# lab2_kapustin_buck.net
KiCad netlist of a schematic drawn in Altium Designer
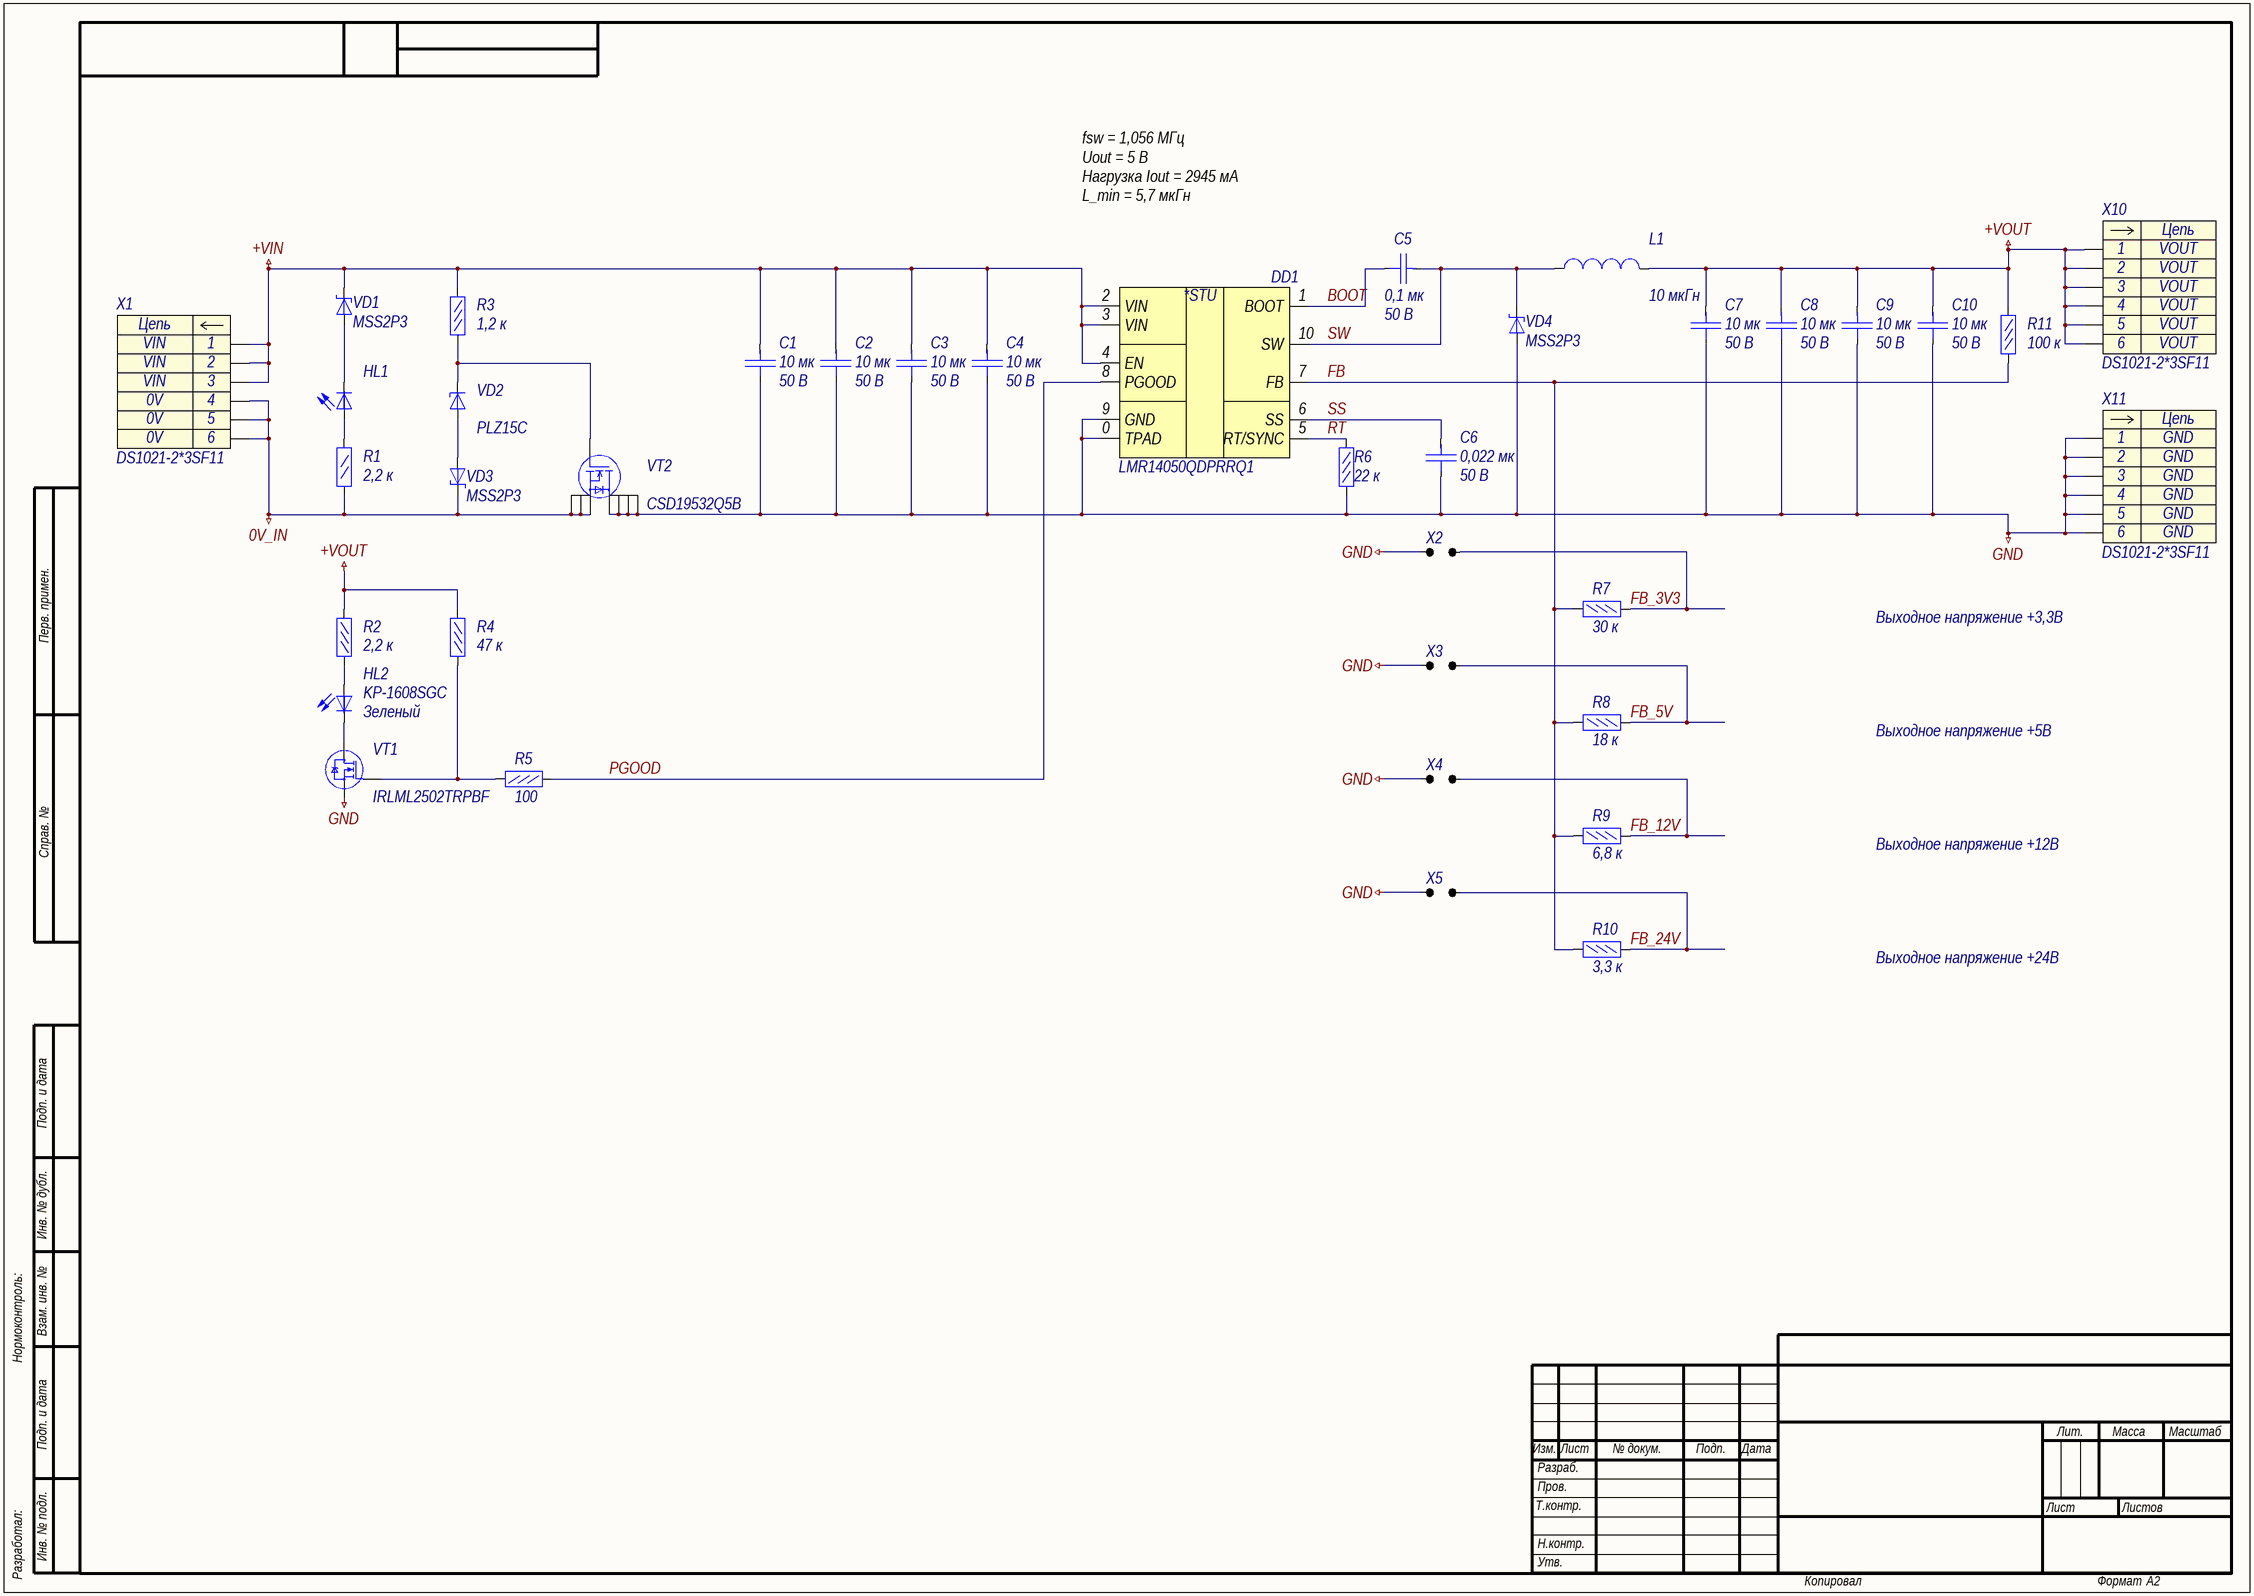
[diagram p0: lab2_kapustin_buck.SchDoc]

(export (version "E")
  (design (tool "Eeschema 10.0.6"))
  (components
    (comp (ref "C1")
      (value "10 мк")
      (footprint "C1206")
      (description "Конденсатор")
      (fields (field (name "НАПРЯЖЕНИЕ") "50 В"))
      (libsource (lib "kravt_lib") (part "c"))
    )
    (comp (ref "C2")
      (value "10 мк")
      (footprint "C1206")
      (description "Конденсатор")
      (fields (field (name "НАПРЯЖЕНИЕ") "50 В"))
      (libsource (lib "kravt_lib") (part "c"))
    )
    (comp (ref "C3")
      (value "10 мк")
      (footprint "C1206")
      (description "Конденсатор")
      (fields (field (name "НАПРЯЖЕНИЕ") "50 В"))
      (libsource (lib "kravt_lib") (part "c"))
    )
    (comp (ref "C4")
      (value "10 мк")
      (footprint "C1206")
      (description "Конденсатор")
      (fields (field (name "НАПРЯЖЕНИЕ") "50 В"))
      (libsource (lib "kravt_lib") (part "c"))
    )
    (comp (ref "C5")
      (value "0,1 мк")
      (footprint "C0603")
      (description "Конденсатор")
      (fields (field (name "НАПРЯЖЕНИЕ") "50 В"))
      (libsource (lib "kravt_lib") (part "c"))
    )
    (comp (ref "C6")
      (value "0,022 мк")
      (footprint "C0603")
      (description "Конденсатор")
      (fields (field (name "НАПРЯЖЕНИЕ") "50 В"))
      (libsource (lib "kravt_lib") (part "c"))
    )
    (comp (ref "C7")
      (value "10 мк")
      (footprint "C1206")
      (description "Конденсатор")
      (fields (field (name "НАПРЯЖЕНИЕ") "50 В"))
      (libsource (lib "kravt_lib") (part "c"))
    )
    (comp (ref "C8")
      (value "10 мк")
      (footprint "C1206")
      (description "Конденсатор")
      (fields (field (name "НАПРЯЖЕНИЕ") "50 В"))
      (libsource (lib "kravt_lib") (part "c"))
    )
    (comp (ref "C9")
      (value "10 мк")
      (footprint "C1206")
      (description "Конденсатор")
      (fields (field (name "НАПРЯЖЕНИЕ") "50 В"))
      (libsource (lib "kravt_lib") (part "c"))
    )
    (comp (ref "C10")
      (value "10 мк")
      (footprint "C1206")
      (description "Конденсатор")
      (fields (field (name "НАПРЯЖЕНИЕ") "50 В"))
      (libsource (lib "kravt_lib") (part "c"))
    )
    (comp (ref "DD1")
      (value "LMR14050QDPRRQ1")
      (footprint "WSON-10")
      (libsource (lib "kravt_lib") (part "LMR14050QDPRRQ1"))
    )
    (comp (ref "HL1")
      (value "KP-1608EC")
      (footprint "D0603")
      (libsource (lib "kravt_lib") (part "DIODE_LED"))
    )
    (comp (ref "HL2")
      (value "KP-1608SGC")
      (footprint "D0603")
      (fields (field (name "НАИМЕНОВАНИЕ") "KP-1608SGC") (field (name "ЦВЕТ") "Зеленый"))
      (libsource (lib "kravt_lib") (part "DIODE_LED"))
    )
    (comp (ref "L1") (value "10 мкГн") (footprint "IHLP2525CZ") (libsource (lib "kravt_lib") (part "L_CORE")))
    (comp (ref "R1")
      (value "2,2 к")
      (footprint "R0805")
      (description "Резистор 0,125Вт")
      (libsource (lib "kravt_lib") (part "R-0.125W"))
    )
    (comp (ref "R2")
      (value "2,2 к")
      (footprint "R0603")
      (description "Резистор 0,063Вт")
      (fields (field (name "НОМИНАЛ") "2,2 к"))
      (libsource (lib "kravt_lib") (part "R-0.063W"))
    )
    (comp (ref "R3")
      (value "1,2 к")
      (footprint "R0603")
      (description "Резистор 0,063Вт")
      (libsource (lib "") (part "R-0.063W_2"))
    )
    (comp (ref "R4")
      (value "47 к")
      (footprint "R0603")
      (description "Резистор 0,063Вт")
      (fields (field (name "НОМИНАЛ") "47 к"))
      (libsource (lib "kravt_lib") (part "R-0.063W"))
    )
    (comp (ref "R5")
      (value "100")
      (footprint "R0603")
      (description "Резистор 0,063Вт")
      (fields (field (name "НОМИНАЛ") "100"))
      (libsource (lib "") (part "R-0.063W_1"))
    )
    (comp (ref "R6")
      (value "22 к")
      (footprint "R0603")
      (description "Резистор 0,063Вт")
      (libsource (lib "") (part "R-0.063W_1"))
    )
    (comp (ref "R7")
      (value "30 к")
      (footprint "R0603")
      (description "Резистор 0,063Вт")
      (libsource (lib "kravt_lib") (part "R-0.063W"))
    )
    (comp (ref "R8")
      (value "18 к")
      (footprint "R0603")
      (description "Резистор 0,063Вт")
      (fields (field (name "НОМИНАЛ") "18 к"))
      (libsource (lib "") (part "R-0.063W_3"))
    )
    (comp (ref "R9")
      (value "6,8 к")
      (footprint "R0603")
      (description "Резистор 0,063Вт")
      (libsource (lib "kravt_lib") (part "R-0.063W"))
    )
    (comp (ref "R10")
      (value "3,3 к")
      (footprint "R0603")
      (description "Резистор 0,063Вт")
      (libsource (lib "kravt_lib") (part "R-0.063W"))
    )
    (comp (ref "R11")
      (value "100 к")
      (footprint "R0603")
      (description "Резистор 0,063Вт")
      (fields (field (name "НОМИНАЛ") "100 к"))
      (libsource (lib "") (part "R-0.063W_2"))
    )
    (comp (ref "VD1")
      (value "MSS2P3")
      (footprint "DO-219AD")
      (libsource (lib "kravt_lib") (part "DIODE_SHOTTKY"))
    )
    (comp (ref "VD2")
      (value "PLZ15C")
      (footprint "DO-219AC")
      (libsource (lib "kravt_lib") (part "DIODE_ZENER"))
    )
    (comp (ref "VD3")
      (value "MSS2P3")
      (footprint "DO-219AD")
      (libsource (lib "kravt_lib") (part "DIODE_SHOTTKY"))
    )
    (comp (ref "VD4")
      (value "MSS2P3")
      (footprint "DO-219AD")
      (libsource (lib "kravt_lib") (part "DIODE_SHOTTKY"))
    )
    (comp (ref "VT1")
      (value "IRLML2502TRPBF")
      (footprint "SOT23-3")
      (libsource (lib "kravt_lib") (part "MOSFET-N-1G-2S-3D"))
    )
    (comp (ref "VT2")
      (value "CSD19532Q5B")
      (footprint "SON-8P")
      (libsource (lib "kravt_lib") (part "MOSFET-N-123S-4G-5678D"))
    )
    (comp (ref "X1")
      (value "DS1021-2*3SF11")
      (footprint "PLS-2,54-2X3-THT-V")
      (libsource (lib "") (part "HEADER-6_PLG_1"))
    )
    (comp (ref "X2")
      (value "Перемычка запаиваемая 3x1")
      (footprint "JUMPER_SOLDERED_3X1")
      (libsource (lib "kravt_lib") (part "JUMPER_SOLDERED"))
    )
    (comp (ref "X3")
      (value "Перемычка запаиваемая 3x1")
      (footprint "JUMPER_SOLDERED_3X1")
      (libsource (lib "kravt_lib") (part "JUMPER_SOLDERED"))
    )
    (comp (ref "X4")
      (value "Перемычка запаиваемая 3x1")
      (footprint "JUMPER_SOLDERED_3X1")
      (libsource (lib "kravt_lib") (part "JUMPER_SOLDERED"))
    )
    (comp (ref "X5")
      (value "Перемычка запаиваемая 3x1")
      (footprint "JUMPER_SOLDERED_3X1")
      (libsource (lib "kravt_lib") (part "JUMPER_SOLDERED"))
    )
    (comp (ref "X10")
      (value "DS1021-2*3SF11")
      (footprint "PLS-2,54-2X3-THT-V")
      (libsource (lib "kravt_lib") (part "HEADER-6_PLG"))
    )
    (comp (ref "X11")
      (value "DS1021-2*3SF11")
      (footprint "PLS-2,54-2X3-THT-V")
      (libsource (lib "kravt_lib") (part "HEADER-6_PLG"))
    )
  )
  (nets
    (net (code "1") (name "+VIN") (class "Default")
      (node (ref "C1") (pin "2") (pinfunction "2_2") (pintype "passive"))
      (node (ref "C2") (pin "2") (pinfunction "2_2") (pintype "passive"))
      (node (ref "C3") (pin "2") (pinfunction "2_2") (pintype "passive"))
      (node (ref "C4") (pin "2") (pinfunction "2_2") (pintype "passive"))
      (node (ref "DD1") (pin "2") (pinfunction "VIN_2") (pintype "passive"))
      (node (ref "DD1") (pin "3") (pinfunction "VIN_3") (pintype "passive"))
      (node (ref "DD1") (pin "4") (pinfunction "EN_4") (pintype "passive"))
      (node (ref "R3") (pin "2") (pinfunction "2_2") (pintype "passive"))
      (node (ref "VD1") (pin "2") (pinfunction "K_2") (pintype "passive"))
      (node (ref "X1") (pin "1") (pinfunction "1_1") (pintype "passive"))
      (node (ref "X1") (pin "2") (pinfunction "2_2") (pintype "passive"))
      (node (ref "X1") (pin "3") (pinfunction "3_3") (pintype "passive"))
    )
    (net (code "2") (name "+VOUT") (class "Default")
      (node (ref "C10") (pin "2") (pinfunction "2_2") (pintype "passive"))
      (node (ref "C7") (pin "2") (pinfunction "2_2") (pintype "passive"))
      (node (ref "C8") (pin "2") (pinfunction "2_2") (pintype "passive"))
      (node (ref "C9") (pin "2") (pinfunction "2_2") (pintype "passive"))
      (node (ref "L1") (pin "2") (pinfunction "2_2") (pintype "passive"))
      (node (ref "R11") (pin "2") (pinfunction "2_2") (pintype "passive"))
      (node (ref "R2") (pin "2") (pinfunction "2_2") (pintype "passive"))
      (node (ref "R4") (pin "2") (pinfunction "2_2") (pintype "passive"))
      (node (ref "X10") (pin "1") (pinfunction "1_1") (pintype "passive"))
      (node (ref "X10") (pin "2") (pinfunction "2_2") (pintype "passive"))
      (node (ref "X10") (pin "3") (pinfunction "3_3") (pintype "passive"))
      (node (ref "X10") (pin "4") (pinfunction "4_4") (pintype "passive"))
      (node (ref "X10") (pin "5") (pinfunction "5_5") (pintype "passive"))
      (node (ref "X10") (pin "6") (pinfunction "6_6") (pintype "passive"))
    )
    (net (code "3") (name "/BOOT") (class "Default")
      (node (ref "C5") (pin "1") (pinfunction "1_1") (pintype "passive"))
      (node (ref "DD1") (pin "1") (pinfunction "BOOT_1") (pintype "passive"))
    )
    (net (code "4") (name "/FB") (class "Default")
      (node (ref "DD1") (pin "7") (pinfunction "FB_7") (pintype "passive"))
      (node (ref "R10") (pin "1") (pinfunction "1_1") (pintype "passive"))
      (node (ref "R11") (pin "1") (pinfunction "1_1") (pintype "passive"))
      (node (ref "R7") (pin "1") (pinfunction "1_1") (pintype "passive"))
      (node (ref "R8") (pin "2") (pinfunction "2_2") (pintype "passive"))
      (node (ref "R9") (pin "1") (pinfunction "1_1") (pintype "passive"))
    )
    (net (code "5") (name "/FB_3V3") (class "Default")
      (node (ref "R7") (pin "2") (pinfunction "2_2") (pintype "passive"))
      (node (ref "X2") (pin "2") (pinfunction "2_2") (pintype "passive"))
    )
    (net (code "6") (name "/FB_5V") (class "Default")
      (node (ref "R8") (pin "1") (pinfunction "1_1") (pintype "passive"))
      (node (ref "X3") (pin "2") (pinfunction "2_2") (pintype "passive"))
    )
    (net (code "7") (name "/FB_12V") (class "Default")
      (node (ref "R9") (pin "2") (pinfunction "2_2") (pintype "passive"))
      (node (ref "X4") (pin "2") (pinfunction "2_2") (pintype "passive"))
    )
    (net (code "8") (name "/FB_24V") (class "Default")
      (node (ref "R10") (pin "2") (pinfunction "2_2") (pintype "passive"))
      (node (ref "X5") (pin "2") (pinfunction "2_2") (pintype "passive"))
    )
    (net (code "9") (name "/PGOOD") (class "Default")
      (node (ref "DD1") (pin "8") (pinfunction "PGOOD_8") (pintype "passive"))
      (node (ref "R5") (pin "1") (pinfunction "1_1") (pintype "passive"))
    )
    (net (code "10") (name "/RT") (class "Default")
      (node (ref "DD1") (pin "5") (pinfunction "RT/SYNC_5") (pintype "passive"))
      (node (ref "R6") (pin "1") (pinfunction "1_1") (pintype "passive"))
    )
    (net (code "11") (name "/SS") (class "Default")
      (node (ref "C6") (pin "2") (pinfunction "2_2") (pintype "passive"))
      (node (ref "DD1") (pin "6") (pinfunction "SS_6") (pintype "passive"))
    )
    (net (code "12") (name "/SW") (class "Default")
      (node (ref "C5") (pin "2") (pinfunction "2_2") (pintype "passive"))
      (node (ref "DD1") (pin "10") (pinfunction "SW_10") (pintype "passive"))
      (node (ref "L1") (pin "1") (pinfunction "1_1") (pintype "passive"))
      (node (ref "VD4") (pin "2") (pinfunction "K_2") (pintype "passive"))
    )
    (net (code "13") (name "0V_IN") (class "Default")
      (node (ref "R1") (pin "1") (pinfunction "1_1") (pintype "passive"))
      (node (ref "VD3") (pin "2") (pinfunction "K_2") (pintype "passive"))
      (node (ref "VT2") (pin "S") (pinfunction "S_S") (pintype "passive"))
      (node (ref "X1") (pin "4") (pinfunction "4_4") (pintype "passive"))
      (node (ref "X1") (pin "5") (pinfunction "5_5") (pintype "passive"))
      (node (ref "X1") (pin "6") (pinfunction "6_6") (pintype "passive"))
    )
    (net (code "14") (name "GND") (class "Default")
      (node (ref "C1") (pin "1") (pinfunction "1_1") (pintype "passive"))
      (node (ref "C10") (pin "1") (pinfunction "1_1") (pintype "passive"))
      (node (ref "C2") (pin "1") (pinfunction "1_1") (pintype "passive"))
      (node (ref "C3") (pin "1") (pinfunction "1_1") (pintype "passive"))
      (node (ref "C4") (pin "1") (pinfunction "1_1") (pintype "passive"))
      (node (ref "C6") (pin "1") (pinfunction "1_1") (pintype "passive"))
      (node (ref "C7") (pin "1") (pinfunction "1_1") (pintype "passive"))
      (node (ref "C8") (pin "1") (pinfunction "1_1") (pintype "passive"))
      (node (ref "C9") (pin "1") (pinfunction "1_1") (pintype "passive"))
      (node (ref "DD1") (pin "0") (pinfunction "TPAD_0") (pintype "passive"))
      (node (ref "DD1") (pin "9") (pinfunction "GND_9") (pintype "passive"))
      (node (ref "R6") (pin "2") (pinfunction "2_2") (pintype "passive"))
      (node (ref "VD4") (pin "1") (pinfunction "A_1") (pintype "passive"))
      (node (ref "VT1") (pin "2") (pinfunction "S_2") (pintype "passive"))
      (node (ref "VT2") (pin "D") (pinfunction "D_D") (pintype "passive"))
      (node (ref "X11") (pin "1") (pinfunction "1_1") (pintype "passive"))
      (node (ref "X11") (pin "2") (pinfunction "2_2") (pintype "passive"))
      (node (ref "X11") (pin "3") (pinfunction "3_3") (pintype "passive"))
      (node (ref "X11") (pin "4") (pinfunction "4_4") (pintype "passive"))
      (node (ref "X11") (pin "5") (pinfunction "5_5") (pintype "passive"))
      (node (ref "X11") (pin "6") (pinfunction "6_6") (pintype "passive"))
      (node (ref "X2") (pin "1") (pinfunction "1_1") (pintype "passive"))
      (node (ref "X3") (pin "1") (pinfunction "1_1") (pintype "passive"))
      (node (ref "X4") (pin "1") (pinfunction "1_1") (pintype "passive"))
      (node (ref "X5") (pin "1") (pinfunction "1_1") (pintype "passive"))
    )
    (net (code "15") (name "Net-(HL1-A)") (class "Default")
      (node (ref "HL1") (pin "1") (pinfunction "A_1") (pintype "passive"))
      (node (ref "R1") (pin "2") (pinfunction "2_2") (pintype "passive"))
    )
    (net (code "16") (name "Net-(HL1-K)") (class "Default")
      (node (ref "HL1") (pin "2") (pinfunction "K_2") (pintype "passive"))
      (node (ref "VD1") (pin "1") (pinfunction "A_1") (pintype "passive"))
    )
    (net (code "17") (name "Net-(HL2-A)") (class "Default")
      (node (ref "HL2") (pin "1") (pinfunction "A_1") (pintype "passive"))
      (node (ref "R2") (pin "1") (pinfunction "1_1") (pintype "passive"))
    )
    (net (code "18") (name "Net-(HL2-K)") (class "Default")
      (node (ref "HL2") (pin "2") (pinfunction "K_2") (pintype "passive"))
      (node (ref "VT1") (pin "3") (pinfunction "D_3") (pintype "passive"))
    )
    (net (code "19") (name "Net-(VD2-A)") (class "Default")
      (node (ref "VD2") (pin "1") (pinfunction "A_1") (pintype "passive"))
      (node (ref "VD3") (pin "1") (pinfunction "A_1") (pintype "passive"))
    )
    (net (code "20") (name "Net-(VD2-K)") (class "Default")
      (node (ref "R3") (pin "1") (pinfunction "1_1") (pintype "passive"))
      (node (ref "VD2") (pin "2") (pinfunction "K_2") (pintype "passive"))
      (node (ref "VT2") (pin "G") (pinfunction "G_G") (pintype "passive"))
    )
    (net (code "21") (name "Net-(VT1-G)") (class "Default")
      (node (ref "R4") (pin "1") (pinfunction "1_1") (pintype "passive"))
      (node (ref "R5") (pin "2") (pinfunction "2_2") (pintype "passive"))
      (node (ref "VT1") (pin "1") (pinfunction "G_1") (pintype "passive"))
    )
  )
)
